# 010_bluetooth.net
KiCad netlist of a schematic drawn in EAGLE
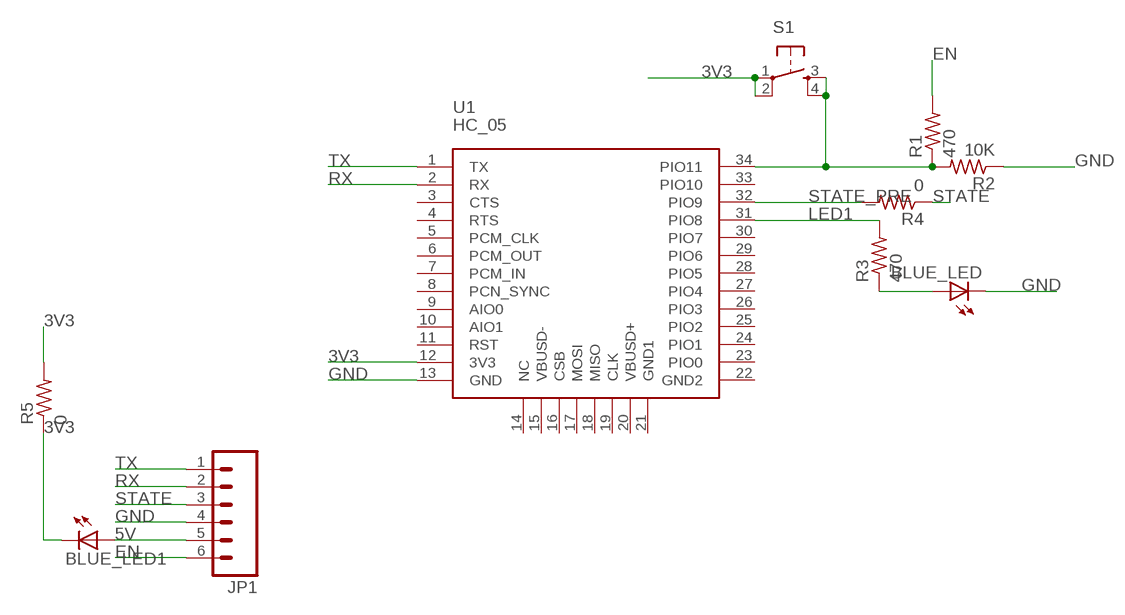
[diagram p0: schematic, sheet 1]

(export (version "E")
  (design (tool "Eeschema 10.0.6"))
  (components
    (comp (ref "BLUE_LED")
      (value "LED1206")
      (footprint "eagle-import:1206")
      (libsource (lib "eagle-import") (part "LED1206"))
    )
    (comp (ref "BLUE_LED1")
      (value "LED1206")
      (footprint "eagle-import:1206")
      (libsource (lib "eagle-import") (part "LED1206"))
    )
    (comp (ref "JP1")
      (value "M06LONGPADS")
      (footprint "eagle-import:1X06_LONGPADS")
      (libsource (lib "eagle-import") (part "M06LONGPADS"))
    )
    (comp (ref "R1")
      (value "470")
      (footprint "eagle-import:1206")
      (libsource (lib "eagle-import") (part "RESISTOR1206"))
    )
    (comp (ref "R2")
      (value "10K")
      (footprint "eagle-import:1206")
      (libsource (lib "eagle-import") (part "RESISTOR1206"))
    )
    (comp (ref "R3")
      (value "470")
      (footprint "eagle-import:1206")
      (libsource (lib "eagle-import") (part "RESISTOR1206"))
    )
    (comp (ref "R4")
      (value "0")
      (footprint "eagle-import:1206")
      (libsource (lib "eagle-import") (part "RESISTOR1206"))
    )
    (comp (ref "R5")
      (value "0")
      (footprint "eagle-import:1206")
      (libsource (lib "eagle-import") (part "RESISTOR1206"))
    )
    (comp (ref "S1")
      (value "6MM_SWITCH6MM_SWITCH")
      (footprint "eagle-import:6MM_SWITCH")
      (libsource (lib "eagle-import") (part "6MM_SWITCH6MM_SWITCH"))
    )
    (comp (ref "U1")
      (value "HC_05")
      (footprint "eagle-import:BLUETOOTH_SMD")
      (libsource (lib "eagle-import") (part "HC_05"))
    )
  )
  (nets
    (net (code "1") (name "/3V3") (class "Default")
      (node (ref "BLUE_LED1") (pin "2") (pinfunction "C_2") (pintype "passive"))
      (node (ref "R5") (pin "1") (pinfunction "1_1") (pintype "passive"))
      (node (ref "R5") (pin "2") (pinfunction "2_2") (pintype "passive"))
      (node (ref "S1") (pin "1") (pinfunction "P_1") (pintype "passive"))
      (node (ref "S1") (pin "2") (pinfunction "P1_2") (pintype "passive"))
      (node (ref "U1") (pin "12") (pinfunction "3V3_12") (pintype "bidirectional"))
    )
    (net (code "2") (name "/5V") (class "Default")
      (node (ref "BLUE_LED1") (pin "1") (pinfunction "A_1") (pintype "passive"))
      (node (ref "JP1") (pin "5") (pinfunction "5_5") (pintype "passive"))
    )
    (net (code "3") (name "/EN") (class "Default")
      (node (ref "JP1") (pin "6") (pinfunction "6_6") (pintype "passive"))
      (node (ref "R1") (pin "2") (pinfunction "2_2") (pintype "passive"))
    )
    (net (code "4") (name "/GND") (class "Default")
      (node (ref "BLUE_LED") (pin "2") (pinfunction "C_2") (pintype "passive"))
      (node (ref "JP1") (pin "4") (pinfunction "4_4") (pintype "passive"))
      (node (ref "R2") (pin "1") (pinfunction "1_1") (pintype "passive"))
      (node (ref "U1") (pin "13") (pinfunction "GND_13") (pintype "bidirectional"))
    )
    (net (code "5") (name "/LED1") (class "Default")
      (node (ref "R3") (pin "2") (pinfunction "2_2") (pintype "passive"))
      (node (ref "U1") (pin "31") (pinfunction "PIO8_31") (pintype "bidirectional"))
    )
    (net (code "6") (name "/RX") (class "Default")
      (node (ref "JP1") (pin "2") (pinfunction "2_2") (pintype "passive"))
      (node (ref "U1") (pin "2") (pinfunction "RX_2") (pintype "bidirectional"))
    )
    (net (code "7") (name "/STATE") (class "Default")
      (node (ref "JP1") (pin "3") (pinfunction "3_3") (pintype "passive"))
      (node (ref "R4") (pin "1") (pinfunction "1_1") (pintype "passive"))
    )
    (net (code "8") (name "/STATE_PRE") (class "Default")
      (node (ref "R4") (pin "2") (pinfunction "2_2") (pintype "passive"))
      (node (ref "U1") (pin "32") (pinfunction "PIO9_32") (pintype "bidirectional"))
    )
    (net (code "9") (name "/TX") (class "Default")
      (node (ref "JP1") (pin "1") (pinfunction "1_1") (pintype "passive"))
      (node (ref "U1") (pin "1") (pinfunction "TX_1") (pintype "bidirectional"))
    )
    (net (code "10") (name "Net-(BLUE_LED-A)") (class "Default")
      (node (ref "BLUE_LED") (pin "1") (pinfunction "A_1") (pintype "passive"))
      (node (ref "R3") (pin "1") (pinfunction "1_1") (pintype "passive"))
    )
    (net (code "11") (name "Net-(S1-S)") (class "Default")
      (node (ref "R1") (pin "1") (pinfunction "1_1") (pintype "passive"))
      (node (ref "R2") (pin "2") (pinfunction "2_2") (pintype "passive"))
      (node (ref "S1") (pin "3") (pinfunction "S_3") (pintype "passive"))
      (node (ref "S1") (pin "4") (pinfunction "S1_4") (pintype "passive"))
      (node (ref "U1") (pin "34") (pinfunction "PIO11_34") (pintype "bidirectional"))
    )
    (net (code "12") (name "unconnected-(U1-AIO0-Pad9)") (class "Default")
      (node (ref "U1") (pin "9") (pinfunction "AIO0_9") (pintype "bidirectional"))
    )
    (net (code "13") (name "unconnected-(U1-AIO1-Pad10)") (class "Default")
      (node (ref "U1") (pin "10") (pinfunction "AIO1_10") (pintype "bidirectional"))
    )
    (net (code "14") (name "unconnected-(U1-CLK-Pad19)") (class "Default")
      (node (ref "U1") (pin "19") (pinfunction "CLK_19") (pintype "bidirectional"))
    )
    (net (code "15") (name "unconnected-(U1-CSB-Pad16)") (class "Default")
      (node (ref "U1") (pin "16") (pinfunction "CSB_16") (pintype "bidirectional"))
    )
    (net (code "16") (name "unconnected-(U1-CTS-Pad3)") (class "Default")
      (node (ref "U1") (pin "3") (pinfunction "CTS_3") (pintype "bidirectional"))
    )
    (net (code "17") (name "unconnected-(U1-GND1-Pad21)") (class "Default")
      (node (ref "U1") (pin "21") (pinfunction "GND1_21") (pintype "bidirectional"))
    )
    (net (code "18") (name "unconnected-(U1-GND2-Pad22)") (class "Default")
      (node (ref "U1") (pin "22") (pinfunction "GND2_22") (pintype "bidirectional"))
    )
    (net (code "19") (name "unconnected-(U1-MISO-Pad18)") (class "Default")
      (node (ref "U1") (pin "18") (pinfunction "MISO_18") (pintype "bidirectional"))
    )
    (net (code "20") (name "unconnected-(U1-MOSI-Pad17)") (class "Default")
      (node (ref "U1") (pin "17") (pinfunction "MOSI_17") (pintype "bidirectional"))
    )
    (net (code "21") (name "unconnected-(U1-NC-Pad14)") (class "Default")
      (node (ref "U1") (pin "14") (pinfunction "NC_14") (pintype "bidirectional"))
    )
    (net (code "22") (name "unconnected-(U1-PCM_CLK-Pad5)") (class "Default")
      (node (ref "U1") (pin "5") (pinfunction "PCM_CLK_5") (pintype "bidirectional"))
    )
    (net (code "23") (name "unconnected-(U1-PCM_IN-Pad7)") (class "Default")
      (node (ref "U1") (pin "7") (pinfunction "PCM_IN_7") (pintype "bidirectional"))
    )
    (net (code "24") (name "unconnected-(U1-PCM_OUT-Pad6)") (class "Default")
      (node (ref "U1") (pin "6") (pinfunction "PCM_OUT_6") (pintype "bidirectional"))
    )
    (net (code "25") (name "unconnected-(U1-PCN_SYNC-Pad8)") (class "Default")
      (node (ref "U1") (pin "8") (pinfunction "PCN_SYNC_8") (pintype "bidirectional"))
    )
    (net (code "26") (name "unconnected-(U1-PIO0-Pad23)") (class "Default")
      (node (ref "U1") (pin "23") (pinfunction "PIO0_23") (pintype "bidirectional"))
    )
    (net (code "27") (name "unconnected-(U1-PIO1-Pad24)") (class "Default")
      (node (ref "U1") (pin "24") (pinfunction "PIO1_24") (pintype "bidirectional"))
    )
    (net (code "28") (name "unconnected-(U1-PIO2-Pad25)") (class "Default")
      (node (ref "U1") (pin "25") (pinfunction "PIO2_25") (pintype "bidirectional"))
    )
    (net (code "29") (name "unconnected-(U1-PIO3-Pad26)") (class "Default")
      (node (ref "U1") (pin "26") (pinfunction "PIO3_26") (pintype "bidirectional"))
    )
    (net (code "30") (name "unconnected-(U1-PIO4-Pad27)") (class "Default")
      (node (ref "U1") (pin "27") (pinfunction "PIO4_27") (pintype "bidirectional"))
    )
    (net (code "31") (name "unconnected-(U1-PIO5-Pad28)") (class "Default")
      (node (ref "U1") (pin "28") (pinfunction "PIO5_28") (pintype "bidirectional"))
    )
    (net (code "32") (name "unconnected-(U1-PIO6-Pad29)") (class "Default")
      (node (ref "U1") (pin "29") (pinfunction "PIO6_29") (pintype "bidirectional"))
    )
    (net (code "33") (name "unconnected-(U1-PIO7-Pad30)") (class "Default")
      (node (ref "U1") (pin "30") (pinfunction "PIO7_30") (pintype "bidirectional"))
    )
    (net (code "34") (name "unconnected-(U1-PIO10-Pad33)") (class "Default")
      (node (ref "U1") (pin "33") (pinfunction "PIO10_33") (pintype "bidirectional"))
    )
    (net (code "35") (name "unconnected-(U1-RST-Pad11)") (class "Default")
      (node (ref "U1") (pin "11") (pinfunction "RST_11") (pintype "bidirectional"))
    )
    (net (code "36") (name "unconnected-(U1-RTS-Pad4)") (class "Default")
      (node (ref "U1") (pin "4") (pinfunction "RTS_4") (pintype "bidirectional"))
    )
    (net (code "37") (name "unconnected-(U1-VBUSD+-Pad20)") (class "Default")
      (node (ref "U1") (pin "20") (pinfunction "VBUSD+_20") (pintype "bidirectional"))
    )
    (net (code "38") (name "unconnected-(U1-VBUSD--Pad15)") (class "Default")
      (node (ref "U1") (pin "15") (pinfunction "VBUSD-_15") (pintype "bidirectional"))
    )
  )
)
